# SparkFun_LoRaSerial_915MHz_-_1W.net
KiCad netlist of a schematic drawn in EAGLE
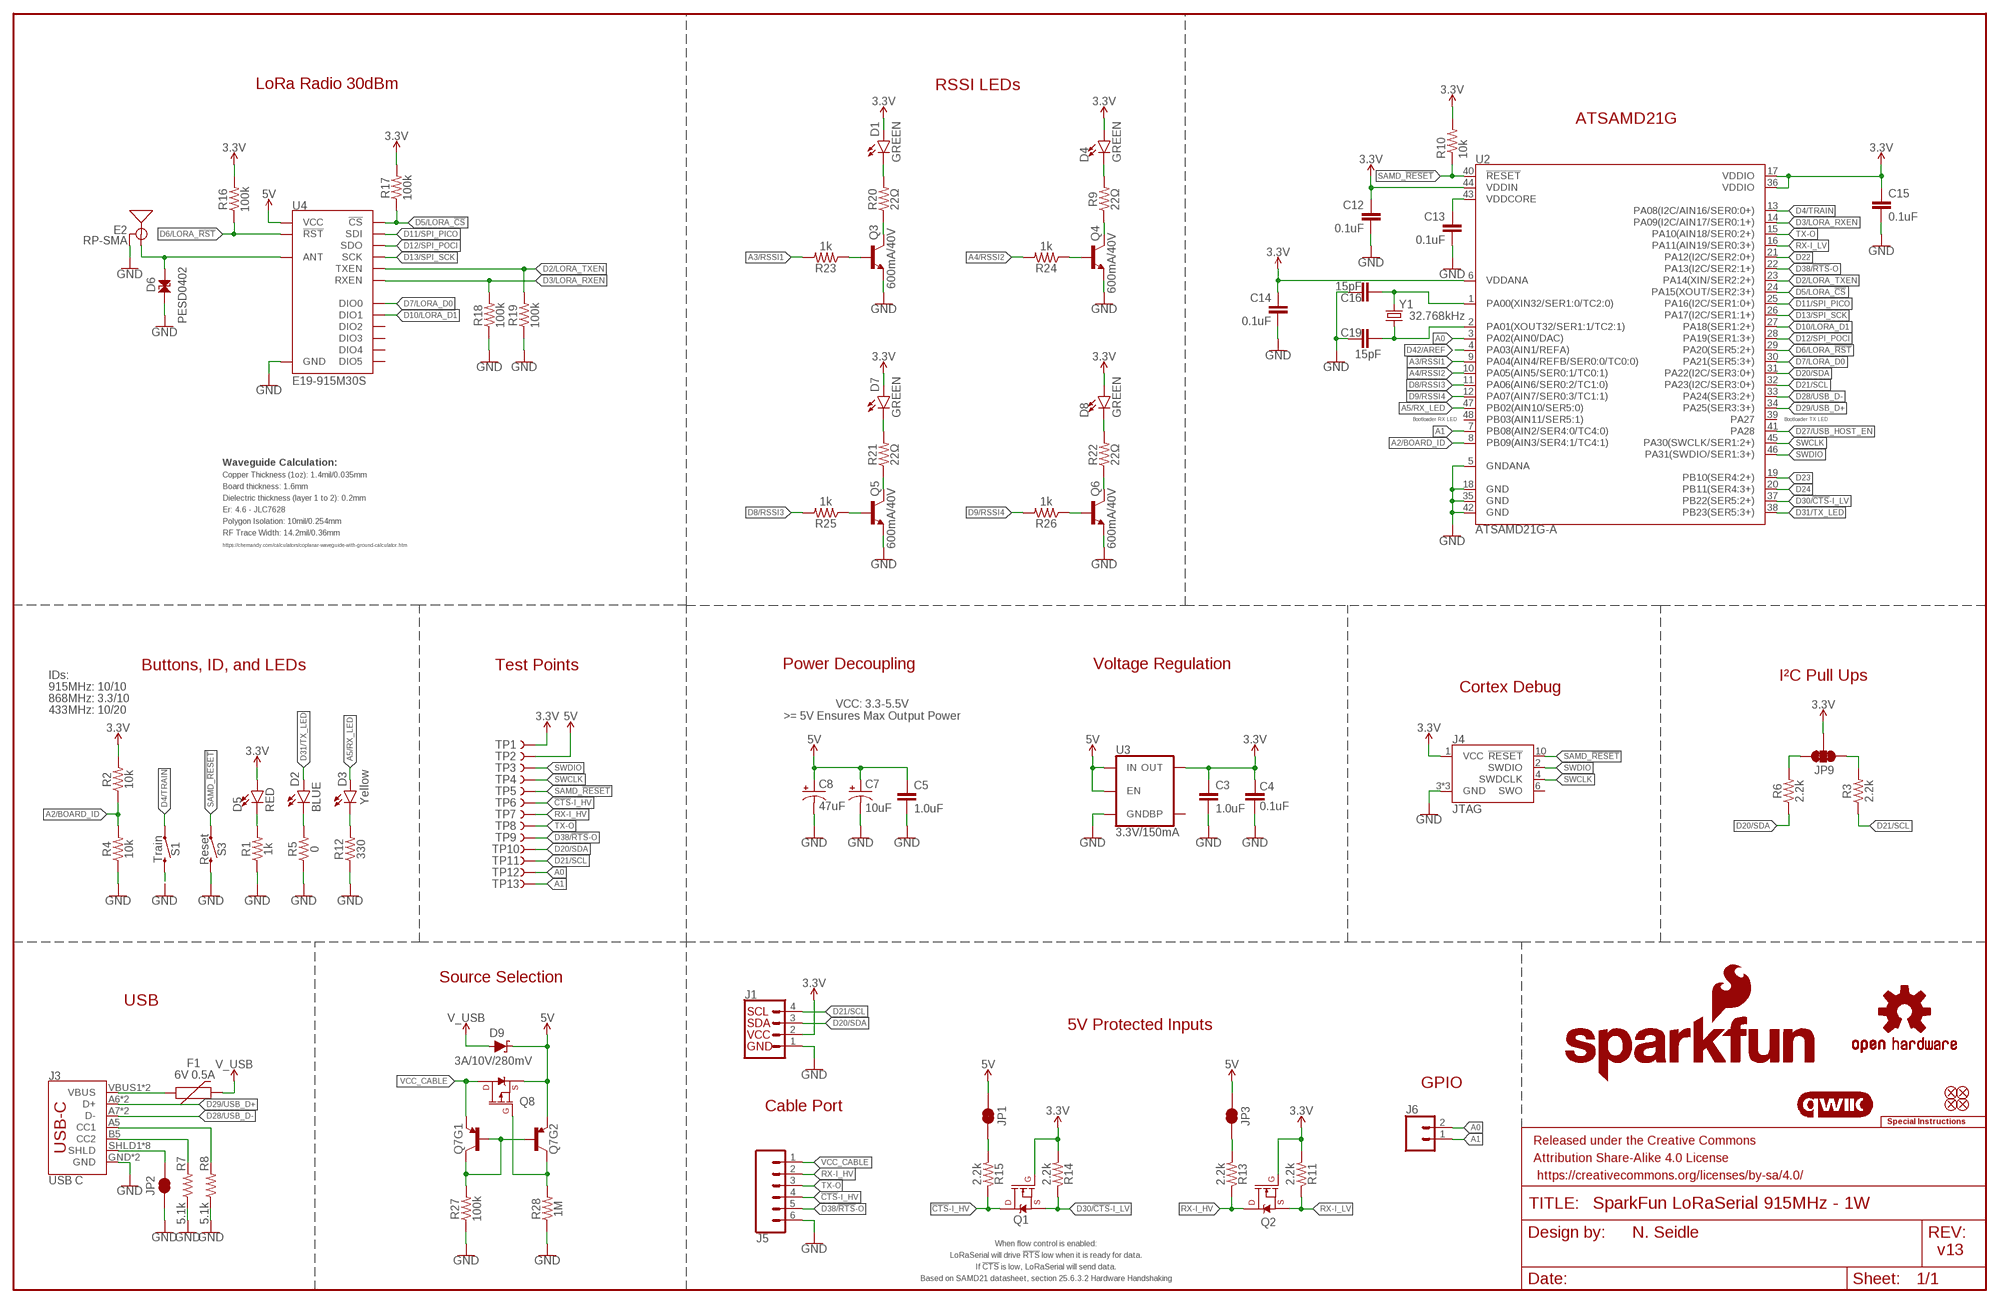
[diagram p0: schematic, sheet 1]

(export (version "E")
  (design (tool "Eeschema 10.0.6"))
  (components
    (comp (ref "C3")
      (value "1.0uF")
      (footprint "eagle-import:0603")
      (libsource (lib "eagle-import") (part "1.0UF-0603-16V-10%-X7R"))
    )
    (comp (ref "C4")
      (value "0.1uF")
      (footprint "eagle-import:0603")
      (libsource (lib "eagle-import") (part "0.1UF-0603-25V-5%"))
    )
    (comp (ref "C5")
      (value "1.0uF")
      (footprint "eagle-import:0603")
      (libsource (lib "eagle-import") (part "1.0UF-0603-16V-10%-X7R"))
    )
    (comp (ref "C7")
      (value "10uF")
      (footprint "eagle-import:EIA3216")
      (libsource (lib "eagle-import") (part "10UF-POLAR-EIA3216-16V-10%(TANT)"))
    )
    (comp (ref "C8")
      (value "47uF")
      (footprint "eagle-import:EIA3528")
      (libsource (lib "eagle-import") (part "47UF-POLAR-EIA3528-10V-10%"))
    )
    (comp (ref "C12")
      (value "0.1uF")
      (footprint "eagle-import:0603")
      (libsource (lib "eagle-import") (part "0.1UF-0603-25V-(+80/-20%)"))
    )
    (comp (ref "C13")
      (value "0.1uF")
      (footprint "eagle-import:0603")
      (libsource (lib "eagle-import") (part "0.1UF-0603-25V-(+80/-20%)"))
    )
    (comp (ref "C14")
      (value "0.1uF")
      (footprint "eagle-import:0603")
      (libsource (lib "eagle-import") (part "0.1UF-0603-25V-(+80/-20%)"))
    )
    (comp (ref "C15")
      (value "0.1uF")
      (footprint "eagle-import:0603")
      (libsource (lib "eagle-import") (part "0.1UF-0603-25V-(+80/-20%)"))
    )
    (comp (ref "C16")
      (value "15pF")
      (footprint "eagle-import:0603")
      (libsource (lib "eagle-import") (part "15PF-0603-50V-5%"))
    )
    (comp (ref "C19")
      (value "15pF")
      (footprint "eagle-import:0603")
      (libsource (lib "eagle-import") (part "15PF-0603-50V-5%"))
    )
    (comp (ref "D1")
      (value "GREEN")
      (footprint "eagle-import:LED-0603")
      (libsource (lib "eagle-import") (part "LED-GREEN0603"))
    )
    (comp (ref "D2")
      (value "BLUE")
      (footprint "eagle-import:LED-0603")
      (libsource (lib "eagle-import") (part "LED-BLUE0603"))
    )
    (comp (ref "D3")
      (value "Yellow")
      (footprint "eagle-import:LED-0603")
      (libsource (lib "eagle-import") (part "LED-YELLOW0603"))
    )
    (comp (ref "D4")
      (value "GREEN")
      (footprint "eagle-import:LED-0603")
      (libsource (lib "eagle-import") (part "LED-GREEN0603"))
    )
    (comp (ref "D5")
      (value "RED")
      (footprint "eagle-import:LED-0603")
      (libsource (lib "eagle-import") (part "LED-RED0603"))
    )
    (comp (ref "D6")
      (value "PESD0402")
      (footprint "eagle-import:0402-TIGHT")
      (libsource (lib "eagle-import") (part "PESD0402-0402T"))
    )
    (comp (ref "D7")
      (value "GREEN")
      (footprint "eagle-import:LED-0603")
      (libsource (lib "eagle-import") (part "LED-GREEN0603"))
    )
    (comp (ref "D8")
      (value "GREEN")
      (footprint "eagle-import:LED-0603")
      (libsource (lib "eagle-import") (part "LED-GREEN0603"))
    )
    (comp (ref "D9")
      (value "3A/10V/280mV")
      (footprint "eagle-import:SOD-323")
      (libsource (lib "eagle-import") (part "DIODE-SCHOTTKY-BAT60A"))
    )
    (comp (ref "E2")
      (value "RP-SMA")
      (footprint "eagle-import:RP-SMA-EDGE")
      (libsource (lib "eagle-import") (part "ANTENNA-SMA-GROUNDEDEDGE_RPSMA"))
    )
    (comp (ref "F1")
      (value "6V 0.5A")
      (footprint "eagle-import:0805")
      (libsource (lib "eagle-import") (part "PPTC_6V500MA"))
    )
    (comp (ref "FID1")
      (value "FIDUCIAL1X2")
      (footprint "eagle-import:FIDUCIAL-1X2")
      (libsource (lib "eagle-import") (part "FIDUCIAL1X2"))
    )
    (comp (ref "FID2")
      (value "FIDUCIAL1X2")
      (footprint "eagle-import:FIDUCIAL-1X2")
      (libsource (lib "eagle-import") (part "FIDUCIAL1X2"))
    )
    (comp (ref "FID3")
      (value "FIDUCIAL1X2")
      (footprint "eagle-import:FIDUCIAL-1X2")
      (libsource (lib "eagle-import") (part "FIDUCIAL1X2"))
    )
    (comp (ref "FID4")
      (value "FIDUCIAL1X2")
      (footprint "eagle-import:FIDUCIAL-1X2")
      (libsource (lib "eagle-import") (part "FIDUCIAL1X2"))
    )
    (comp (ref "FRAME3")
      (value "FRAME-LEDGER")
      (footprint "eagle-import:CREATIVE_COMMONS")
      (libsource (lib "eagle-import") (part "FRAME-LEDGER"))
    )
    (comp (ref "J1")
      (value "QWIIC_RIGHT_ANGLE")
      (footprint "eagle-import:JST04_1MM_RA")
      (libsource (lib "eagle-import") (part "QWIIC_CONNECTORJS-1MM"))
    )
    (comp (ref "J3")
      (value "USB C")
      (footprint "eagle-import:USB-C-16P")
      (libsource (lib "eagle-import") (part "USB_C16PIN"))
    )
    (comp (ref "J4")
      (value "JTAG")
      (footprint "eagle-import:2X5-PTH-1.27MM-NO_SILK")
      (libsource (lib "eagle-import") (part "CORTEX_JTAG_DEBUG_MINIMUM_PTH_NS"))
    )
    (comp (ref "J5")
      (value "CONN_06JST-SMD-LOCKING")
      (footprint "eagle-import:JST-6-SMD-1.25MM-LOCKING")
      (libsource (lib "eagle-import") (part "CONN_06JST-SMD-LOCKING"))
    )
    (comp (ref "J6")
      (value "CONN_021X02_NO_SILK")
      (footprint "eagle-import:1X02_NO_SILK")
      (libsource (lib "eagle-import") (part "CONN_021X02_NO_SILK"))
    )
    (comp (ref "JP1")
      (value "JUMPER-SMT_2_NC_TRACE_SILK")
      (footprint "eagle-import:SMT-JUMPER_2_NC_TRACE_SILK")
      (libsource (lib "eagle-import") (part "JUMPER-SMT_2_NC_TRACE_SILK"))
    )
    (comp (ref "JP2")
      (value "JUMPER-SMT_2_NC_TRACE_SILK")
      (footprint "eagle-import:SMT-JUMPER_2_NC_TRACE_SILK")
      (libsource (lib "eagle-import") (part "JUMPER-SMT_2_NC_TRACE_SILK"))
    )
    (comp (ref "JP3")
      (value "JUMPER-SMT_2_NC_TRACE_SILK")
      (footprint "eagle-import:SMT-JUMPER_2_NC_TRACE_SILK")
      (libsource (lib "eagle-import") (part "JUMPER-SMT_2_NC_TRACE_SILK"))
    )
    (comp (ref "JP9")
      (value "JUMPER-SMT_3_2-NC_TRACE_SILK")
      (footprint "eagle-import:SMT-JUMPER_3_2-NC_TRACE_SILK")
      (libsource (lib "eagle-import") (part "JUMPER-SMT_3_2-NC_TRACE_SILK"))
    )
    (comp (ref "LOGO1")
      (value "SPECIAL_INSTRUCTIONS-ORDERING")
      (footprint "eagle-import:ORDERING_INSTRUCTIONS")
      (libsource (lib "eagle-import") (part "SPECIAL_INSTRUCTIONS-ORDERING"))
    )
    (comp (ref "LOGO2")
      (value "SFE_LOGO_NAME_FLAME9_MM")
      (footprint "eagle-import:SFE_LOGO_NAME_FLAME_9MM")
      (libsource (lib "eagle-import") (part "SFE_LOGO_NAME_FLAME9_MM"))
    )
    (comp (ref "LOGO3")
      (value "QWIIC_LOGO_CONNECTOR")
      (footprint "eagle-import:QWIIC_5.5MM")
      (libsource (lib "eagle-import") (part "QWIIC_LOGO_CONNECTOR"))
    )
    (comp (ref "LOGO4")
      (value "OSHW-LOGOMINI")
      (footprint "eagle-import:OSHW-LOGO-MINI")
      (libsource (lib "eagle-import") (part "OSHW-LOGOMINI"))
    )
    (comp (ref "LOGO5")
      (value "SFE_LOGO_NAME9_MM")
      (footprint "eagle-import:SFE_LOGO_NAME_9MM")
      (libsource (lib "eagle-import") (part "SFE_LOGO_NAME9_MM"))
    )
    (comp (ref "Q1")
      (value "20V/0.2A/8MHz/1.2Ω/1Vth")
      (footprint "eagle-import:SOT-416FL")
      (libsource (lib "eagle-import") (part "MOSFET-NCH-RE1C002UNTCL"))
    )
    (comp (ref "Q2")
      (value "20V/0.2A/8MHz/1.2Ω/1Vth")
      (footprint "eagle-import:SOT-416FL")
      (libsource (lib "eagle-import") (part "MOSFET-NCH-RE1C002UNTCL"))
    )
    (comp (ref "Q3")
      (value "600mA/40V")
      (footprint "eagle-import:SOT23-3")
      (libsource (lib "eagle-import") (part "TRANS_NPN-MMBT2222AL"))
    )
    (comp (ref "Q4")
      (value "600mA/40V")
      (footprint "eagle-import:SOT23-3")
      (libsource (lib "eagle-import") (part "TRANS_NPN-MMBT2222AL"))
    )
    (comp (ref "Q5")
      (value "600mA/40V")
      (footprint "eagle-import:SOT23-3")
      (libsource (lib "eagle-import") (part "TRANS_NPN-MMBT2222AL"))
    )
    (comp (ref "Q6")
      (value "600mA/40V")
      (footprint "eagle-import:SOT23-3")
      (libsource (lib "eagle-import") (part "TRANS_NPN-MMBT2222AL"))
    )
    (comp (ref "Q7")
      (value "TRANS_PNP_DUALSOT-363")
      (footprint "eagle-import:SOT363_PHILIPS")
      (libsource (lib "eagle-import") (part "TRANS_PNP_DUALSOT-363"))
    )
    (comp (ref "Q8")
      (value "20V/4.2A/52mΩ/1.4W")
      (footprint "eagle-import:SOT23-3")
      (libsource (lib "eagle-import") (part "MOSFET_PCH-DMG2305UX-7"))
    )
    (comp (ref "R1")
      (value "1k")
      (footprint "eagle-import:0603")
      (libsource (lib "eagle-import") (part "1KOHM-0603-1/10W-1%"))
    )
    (comp (ref "R2")
      (value "10k")
      (footprint "eagle-import:0603")
      (libsource (lib "eagle-import") (part "10KOHM-0603-1/10W-1%"))
    )
    (comp (ref "R3")
      (value "2.2k")
      (footprint "eagle-import:0603")
      (libsource (lib "eagle-import") (part "2.2KOHM-0603-1/10W-1%"))
    )
    (comp (ref "R4")
      (value "10k")
      (footprint "eagle-import:0603")
      (libsource (lib "eagle-import") (part "10KOHM-0603-1/10W-1%"))
    )
    (comp (ref "R5")
      (value "0")
      (footprint "eagle-import:0603")
      (libsource (lib "eagle-import") (part "0OHM-0603-1/10W"))
    )
    (comp (ref "R6")
      (value "2.2k")
      (footprint "eagle-import:0603")
      (libsource (lib "eagle-import") (part "2.2KOHM-0603-1/10W-1%"))
    )
    (comp (ref "R7")
      (value "5.1k")
      (footprint "eagle-import:0603")
      (libsource (lib "eagle-import") (part "5.1KOHM5.1KOHM-0603-1/10W-1%"))
    )
    (comp (ref "R8")
      (value "5.1k")
      (footprint "eagle-import:0603")
      (libsource (lib "eagle-import") (part "5.1KOHM5.1KOHM-0603-1/10W-1%"))
    )
    (comp (ref "R9")
      (value "22Ω")
      (footprint "eagle-import:0603")
      (libsource (lib "eagle-import") (part "22OHM-0603-1/10W-1%"))
    )
    (comp (ref "R10")
      (value "10k")
      (footprint "eagle-import:0603")
      (libsource (lib "eagle-import") (part "10KOHM-0603-1/10W-1%"))
    )
    (comp (ref "R11")
      (value "2.2k")
      (footprint "eagle-import:0603")
      (libsource (lib "eagle-import") (part "2.2KOHM-0603-1/10W-1%"))
    )
    (comp (ref "R12")
      (value "330")
      (footprint "eagle-import:0603")
      (libsource (lib "eagle-import") (part "330OHM-0603-1/10W-1%"))
    )
    (comp (ref "R13")
      (value "2.2k")
      (footprint "eagle-import:0603")
      (libsource (lib "eagle-import") (part "2.2KOHM-0603-1/10W-1%"))
    )
    (comp (ref "R14")
      (value "2.2k")
      (footprint "eagle-import:0603")
      (libsource (lib "eagle-import") (part "2.2KOHM-0603-1/10W-1%"))
    )
    (comp (ref "R15")
      (value "2.2k")
      (footprint "eagle-import:0603")
      (libsource (lib "eagle-import") (part "2.2KOHM-0603-1/10W-1%"))
    )
    (comp (ref "R16")
      (value "100k")
      (footprint "eagle-import:0603")
      (libsource (lib "eagle-import") (part "100KOHM-0603-1/10W-1%"))
    )
    (comp (ref "R17")
      (value "100k")
      (footprint "eagle-import:0603")
      (libsource (lib "eagle-import") (part "100KOHM-0603-1/10W-1%"))
    )
    (comp (ref "R18")
      (value "100k")
      (footprint "eagle-import:0603")
      (libsource (lib "eagle-import") (part "100KOHM-0603-1/10W-1%"))
    )
    (comp (ref "R19")
      (value "100k")
      (footprint "eagle-import:0603")
      (libsource (lib "eagle-import") (part "100KOHM-0603-1/10W-1%"))
    )
    (comp (ref "R20")
      (value "22Ω")
      (footprint "eagle-import:0603")
      (libsource (lib "eagle-import") (part "22OHM-0603-1/10W-1%"))
    )
    (comp (ref "R21")
      (value "22Ω")
      (footprint "eagle-import:0603")
      (libsource (lib "eagle-import") (part "22OHM-0603-1/10W-1%"))
    )
    (comp (ref "R22")
      (value "22Ω")
      (footprint "eagle-import:0603")
      (libsource (lib "eagle-import") (part "22OHM-0603-1/10W-1%"))
    )
    (comp (ref "R23")
      (value "1k")
      (footprint "eagle-import:0603")
      (libsource (lib "eagle-import") (part "1KOHM-0603-1/10W-1%"))
    )
    (comp (ref "R24")
      (value "1k")
      (footprint "eagle-import:0603")
      (libsource (lib "eagle-import") (part "1KOHM-0603-1/10W-1%"))
    )
    (comp (ref "R25")
      (value "1k")
      (footprint "eagle-import:0603")
      (libsource (lib "eagle-import") (part "1KOHM-0603-1/10W-1%"))
    )
    (comp (ref "R26")
      (value "1k")
      (footprint "eagle-import:0603")
      (libsource (lib "eagle-import") (part "1KOHM-0603-1/10W-1%"))
    )
    (comp (ref "R27")
      (value "100k")
      (footprint "eagle-import:0603")
      (libsource (lib "eagle-import") (part "100KOHM-0603-1/10W-1%"))
    )
    (comp (ref "R28")
      (value "1M")
      (footprint "eagle-import:0603")
      (libsource (lib "eagle-import") (part "1MOHM-0603-1/4W-5%"))
    )
    (comp (ref "S1")
      (value "Train")
      (footprint "eagle-import:TACTILE_SWITCH_SMD_RIGHT_ANGLE")
      (libsource (lib "eagle-import") (part "MOMENTARY-SWITCH-SPST-SMD-RIGHT-ANGLE"))
    )
    (comp (ref "S3")
      (value "Reset")
      (footprint "eagle-import:TACTILE_SWITCH_SMD_5.2MM")
      (libsource (lib "eagle-import") (part "MOMENTARY-SWITCH-SPST-SMD-5.2-TALL-REDUNDANT"))
    )
    (comp (ref "TP1")
      (value "TEST-POINT3X5")
      (footprint "eagle-import:PAD.03X.05")
      (libsource (lib "eagle-import") (part "TEST-POINT3X5"))
    )
    (comp (ref "TP2")
      (value "TEST-POINT3X5")
      (footprint "eagle-import:PAD.03X.05")
      (libsource (lib "eagle-import") (part "TEST-POINT3X5"))
    )
    (comp (ref "TP3")
      (value "TEST-POINT3X5")
      (footprint "eagle-import:PAD.03X.05")
      (libsource (lib "eagle-import") (part "TEST-POINT3X5"))
    )
    (comp (ref "TP4")
      (value "TEST-POINT3X5")
      (footprint "eagle-import:PAD.03X.05")
      (libsource (lib "eagle-import") (part "TEST-POINT3X5"))
    )
    (comp (ref "TP5")
      (value "TEST-POINT3X5")
      (footprint "eagle-import:PAD.03X.05")
      (libsource (lib "eagle-import") (part "TEST-POINT3X5"))
    )
    (comp (ref "TP6")
      (value "TEST-POINT3X5")
      (footprint "eagle-import:PAD.03X.05")
      (libsource (lib "eagle-import") (part "TEST-POINT3X5"))
    )
    (comp (ref "TP7")
      (value "TEST-POINT3X5")
      (footprint "eagle-import:PAD.03X.05")
      (libsource (lib "eagle-import") (part "TEST-POINT3X5"))
    )
    (comp (ref "TP8")
      (value "TEST-POINT3X5")
      (footprint "eagle-import:PAD.03X.05")
      (libsource (lib "eagle-import") (part "TEST-POINT3X5"))
    )
    (comp (ref "TP9")
      (value "TEST-POINT3X5")
      (footprint "eagle-import:PAD.03X.05")
      (libsource (lib "eagle-import") (part "TEST-POINT3X5"))
    )
    (comp (ref "TP10")
      (value "TEST-POINT3X5")
      (footprint "eagle-import:PAD.03X.05")
      (libsource (lib "eagle-import") (part "TEST-POINT3X5"))
    )
    (comp (ref "TP11")
      (value "TEST-POINT3X5")
      (footprint "eagle-import:PAD.03X.05")
      (libsource (lib "eagle-import") (part "TEST-POINT3X5"))
    )
    (comp (ref "TP12")
      (value "TEST-POINT3X5")
      (footprint "eagle-import:PAD.03X.05")
      (libsource (lib "eagle-import") (part "TEST-POINT3X5"))
    )
    (comp (ref "TP13")
      (value "TEST-POINT3X5")
      (footprint "eagle-import:PAD.03X.05")
      (libsource (lib "eagle-import") (part "TEST-POINT3X5"))
    )
    (comp (ref "U2")
      (value "ATSAMD21G-A")
      (footprint "eagle-import:TQFP-48")
      (libsource (lib "eagle-import") (part "ATSAMD21G-A"))
    )
    (comp (ref "U3")
      (value "3.3V/150mA")
      (footprint "eagle-import:SOT23-5")
      (libsource (lib "eagle-import") (part "V_REG_MIC52053.3V"))
    )
    (comp (ref "U4")
      (value "E19-915M30S")
      (footprint "eagle-import:E19-915M30S")
      (libsource (lib "eagle-import") (part "LORA-E19915MHZ"))
    )
    (comp (ref "Y1")
      (value "32.768kHz")
      (footprint "eagle-import:CRYSTAL-SMD-3.2X1.5MM")
      (libsource (lib "eagle-import") (part "CRYSTAL3.2X1.5MM"))
    )
  )
  (nets
    (net (code "1") (name "/D5{slash}LORA_~{CS}") (class "Default")
      (node (ref "R17") (pin "1") (pinfunction "1_1") (pintype "passive"))
      (node (ref "U2") (pin "24") (pinfunction "PA15(XOUT/SER2:3+)_24") (pintype "bidirectional"))
      (node (ref "U4") (pin "15") (pinfunction "~{CS}_15") (pintype "bidirectional"))
    )
    (net (code "2") (name "/D6{slash}LORA_~{RST}") (class "Default")
      (node (ref "R16") (pin "1") (pinfunction "1_1") (pintype "passive"))
      (node (ref "U2") (pin "29") (pinfunction "PA20(SER5:2+)_29") (pintype "bidirectional"))
      (node (ref "U4") (pin "8") (pinfunction "~{RST}_8") (pintype "bidirectional"))
    )
    (net (code "3") (name "/D30{slash}~{CTS}-I_LV") (class "Default")
      (node (ref "Q1") (pin "2") (pinfunction "S_2") (pintype "bidirectional"))
      (node (ref "R14") (pin "1") (pinfunction "1_1") (pintype "passive"))
      (node (ref "U2") (pin "37") (pinfunction "PB22(SER5:2+)_37") (pintype "bidirectional"))
    )
    (net (code "4") (name "/D38{slash}~{RTS}-O") (class "Default")
      (node (ref "J5") (pin "5") (pinfunction "5_5") (pintype "passive"))
      (node (ref "TP9") (pin "1") (pinfunction "1_1") (pintype "bidirectional"))
      (node (ref "U2") (pin "22") (pinfunction "PA13(I2C/SER2:1+)_22") (pintype "bidirectional"))
    )
    (net (code "5") (name "/SAMD_~{RESET}") (class "Default")
      (node (ref "J4") (pin "10") (pinfunction "~{RESET}_10") (pintype "bidirectional"))
      (node (ref "R10") (pin "1") (pinfunction "1_1") (pintype "passive"))
      (node (ref "S3") (pin "1") (pinfunction "1_1") (pintype "passive"))
      (node (ref "S3") (pin "2") (pinfunction "1_2") (pintype "passive"))
      (node (ref "TP5") (pin "1") (pinfunction "1_1") (pintype "bidirectional"))
      (node (ref "U2") (pin "40") (pinfunction "~{RESET}_40") (pintype "bidirectional"))
    )
    (net (code "6") (name "/~{CTS}-I_HV") (class "Default")
      (node (ref "J5") (pin "4") (pinfunction "4_4") (pintype "passive"))
      (node (ref "Q1") (pin "3") (pinfunction "D_3") (pintype "bidirectional"))
      (node (ref "R15") (pin "1") (pinfunction "1_1") (pintype "passive"))
      (node (ref "TP6") (pin "1") (pinfunction "1_1") (pintype "bidirectional"))
    )
    (net (code "7") (name "3.3V") (class "Default")
      (node (ref "C12") (pin "1") (pinfunction "1_1") (pintype "passive"))
      (node (ref "C14") (pin "1") (pinfunction "1_1") (pintype "passive"))
      (node (ref "C15") (pin "1") (pinfunction "1_1") (pintype "passive"))
      (node (ref "C3") (pin "1") (pinfunction "1_1") (pintype "passive"))
      (node (ref "C4") (pin "2") (pinfunction "2_2") (pintype "passive"))
      (node (ref "D1") (pin "A") (pinfunction "A_A") (pintype "passive"))
      (node (ref "D4") (pin "A") (pinfunction "A_A") (pintype "passive"))
      (node (ref "D5") (pin "A") (pinfunction "A_A") (pintype "passive"))
      (node (ref "D7") (pin "A") (pinfunction "A_A") (pintype "passive"))
      (node (ref "D8") (pin "A") (pinfunction "A_A") (pintype "passive"))
      (node (ref "J1") (pin "2") (pinfunction "2_2") (pintype "power_in"))
      (node (ref "J4") (pin "1") (pinfunction "VCC_1") (pintype "bidirectional"))
      (node (ref "JP9") (pin "2") (pinfunction "2_2") (pintype "passive"))
      (node (ref "Q1") (pin "1") (pinfunction "G_1") (pintype "bidirectional"))
      (node (ref "Q2") (pin "1") (pinfunction "G_1") (pintype "bidirectional"))
      (node (ref "R10") (pin "2") (pinfunction "2_2") (pintype "passive"))
      (node (ref "R11") (pin "2") (pinfunction "2_2") (pintype "passive"))
      (node (ref "R14") (pin "2") (pinfunction "2_2") (pintype "passive"))
      (node (ref "R16") (pin "2") (pinfunction "2_2") (pintype "passive"))
      (node (ref "R17") (pin "2") (pinfunction "2_2") (pintype "passive"))
      (node (ref "R2") (pin "2") (pinfunction "2_2") (pintype "passive"))
      (node (ref "TP1") (pin "1") (pinfunction "1_1") (pintype "bidirectional"))
      (node (ref "U2") (pin "17") (pinfunction "VDDIO_17") (pintype "bidirectional"))
      (node (ref "U2") (pin "36") (pinfunction "VDDIO_36") (pintype "bidirectional"))
      (node (ref "U2") (pin "44") (pinfunction "VDDIN_44") (pintype "bidirectional"))
      (node (ref "U2") (pin "6") (pinfunction "VDDANA_6") (pintype "bidirectional"))
      (node (ref "U3") (pin "5") (pinfunction "OUT_5") (pintype "passive"))
    )
    (net (code "8") (name "5V") (class "Default")
      (node (ref "C5") (pin "1") (pinfunction "1_1") (pintype "passive"))
      (node (ref "C7") (pin "+") (pinfunction "+_+") (pintype "passive"))
      (node (ref "C8") (pin "A") (pinfunction "+_A") (pintype "passive"))
      (node (ref "D9") (pin "C") (pinfunction "C_C") (pintype "passive"))
      (node (ref "JP1") (pin "2") (pinfunction "2_2") (pintype "passive"))
      (node (ref "JP3") (pin "2") (pinfunction "2_2") (pintype "passive"))
      (node (ref "Q7") (pin "4") (pinfunction "E_4") (pintype "passive"))
      (node (ref "Q8") (pin "2") (pinfunction "S_2") (pintype "bidirectional"))
      (node (ref "TP2") (pin "1") (pinfunction "1_1") (pintype "bidirectional"))
      (node (ref "U3") (pin "1") (pinfunction "IN_1") (pintype "input"))
      (node (ref "U3") (pin "3") (pinfunction "EN_3") (pintype "input"))
      (node (ref "U4") (pin "11") (pinfunction "VCC_11") (pintype "bidirectional"))
    )
    (net (code "9") (name "A0") (class "Default")
      (node (ref "J6") (pin "2") (pinfunction "2_2") (pintype "passive"))
      (node (ref "TP12") (pin "1") (pinfunction "1_1") (pintype "bidirectional"))
      (node (ref "U2") (pin "3") (pinfunction "PA02(AIN0/DAC)_3") (pintype "bidirectional"))
    )
    (net (code "10") (name "A1") (class "Default")
      (node (ref "J6") (pin "1") (pinfunction "1_1") (pintype "passive"))
      (node (ref "TP13") (pin "1") (pinfunction "1_1") (pintype "bidirectional"))
      (node (ref "U2") (pin "7") (pinfunction "PB08(AIN2/SER4:0/TC4:0)_7") (pintype "bidirectional"))
    )
    (net (code "11") (name "A2{slash}BOARD_ID") (class "Default")
      (node (ref "R2") (pin "1") (pinfunction "1_1") (pintype "passive"))
      (node (ref "R4") (pin "2") (pinfunction "2_2") (pintype "passive"))
      (node (ref "U2") (pin "8") (pinfunction "PB09(AIN3/SER4:1/TC4:1)_8") (pintype "bidirectional"))
    )
    (net (code "12") (name "A3{slash}RSSI1") (class "Default")
      (node (ref "R23") (pin "2") (pinfunction "2_2") (pintype "passive"))
      (node (ref "U2") (pin "9") (pinfunction "PA04(AIN4/REFB/SER0:0/TC0:0)_9") (pintype "bidirectional"))
    )
    (net (code "13") (name "A4{slash}RSSI2") (class "Default")
      (node (ref "R24") (pin "2") (pinfunction "2_2") (pintype "passive"))
      (node (ref "U2") (pin "10") (pinfunction "PA05(AIN5/SER0:1/TC0:1)_10") (pintype "bidirectional"))
    )
    (net (code "14") (name "A5{slash}RX_LED") (class "Default")
      (node (ref "D3") (pin "A") (pinfunction "A_A") (pintype "passive"))
      (node (ref "U2") (pin "47") (pinfunction "PB02(AIN10/SER5:0)_47") (pintype "bidirectional"))
    )
    (net (code "15") (name "D2{slash}LORA_TXEN") (class "Default")
      (node (ref "R19") (pin "2") (pinfunction "2_2") (pintype "passive"))
      (node (ref "U2") (pin "23") (pinfunction "PA14(XIN/SER2:2+)_23") (pintype "bidirectional"))
      (node (ref "U4") (pin "16") (pinfunction "TXEN_16") (pintype "bidirectional"))
    )
    (net (code "16") (name "D3{slash}LORA_RXEN") (class "Default")
      (node (ref "R18") (pin "2") (pinfunction "2_2") (pintype "passive"))
      (node (ref "U2") (pin "14") (pinfunction "PA09(I2C/AIN17/SER0:1+)_14") (pintype "bidirectional"))
      (node (ref "U4") (pin "17") (pinfunction "RXEN_17") (pintype "bidirectional"))
    )
    (net (code "17") (name "D4{slash}TRAIN") (class "Default")
      (node (ref "S1") (pin "1") (pinfunction "1_1") (pintype "passive"))
      (node (ref "U2") (pin "13") (pinfunction "PA08(I2C/AIN16/SER0:0+)_13") (pintype "bidirectional"))
    )
    (net (code "18") (name "D7{slash}LORA_D0") (class "Default")
      (node (ref "U2") (pin "30") (pinfunction "PA21(SER5:3+)_30") (pintype "bidirectional"))
      (node (ref "U4") (pin "7") (pinfunction "DIO0_7") (pintype "bidirectional"))
    )
    (net (code "19") (name "D8{slash}RSSI3") (class "Default")
      (node (ref "R25") (pin "2") (pinfunction "2_2") (pintype "passive"))
      (node (ref "U2") (pin "11") (pinfunction "PA06(AIN6/SER0:2/TC1:0)_11") (pintype "bidirectional"))
    )
    (net (code "20") (name "D9{slash}RSSI4") (class "Default")
      (node (ref "R26") (pin "2") (pinfunction "2_2") (pintype "passive"))
      (node (ref "U2") (pin "12") (pinfunction "PA07(AIN7/SER0:3/TC1:1)_12") (pintype "bidirectional"))
    )
    (net (code "21") (name "D10{slash}LORA_D1") (class "Default")
      (node (ref "U2") (pin "27") (pinfunction "PA18(SER1:2+)_27") (pintype "bidirectional"))
      (node (ref "U4") (pin "6") (pinfunction "DIO1_6") (pintype "bidirectional"))
    )
    (net (code "22") (name "D11{slash}SPI_PICO") (class "Default")
      (node (ref "U2") (pin "25") (pinfunction "PA16(I2C/SER1:0+)_25") (pintype "bidirectional"))
      (node (ref "U4") (pin "14") (pinfunction "SDI_14") (pintype "bidirectional"))
    )
    (net (code "23") (name "D12{slash}SPI_POCI") (class "Default")
      (node (ref "U2") (pin "28") (pinfunction "PA19(SER1:3+)_28") (pintype "bidirectional"))
      (node (ref "U4") (pin "13") (pinfunction "SDO_13") (pintype "bidirectional"))
    )
    (net (code "24") (name "D13{slash}SPI_SCK") (class "Default")
      (node (ref "U2") (pin "26") (pinfunction "PA17(I2C/SER1:1+)_26") (pintype "bidirectional"))
      (node (ref "U4") (pin "12") (pinfunction "SCK_12") (pintype "bidirectional"))
    )
    (net (code "25") (name "D20{slash}SDA") (class "Default")
      (node (ref "J1") (pin "3") (pinfunction "3_3") (pintype "passive"))
      (node (ref "R6") (pin "1") (pinfunction "1_1") (pintype "passive"))
      (node (ref "TP10") (pin "1") (pinfunction "1_1") (pintype "bidirectional"))
      (node (ref "U2") (pin "31") (pinfunction "PA22(I2C/SER3:0+)_31") (pintype "bidirectional"))
    )
    (net (code "26") (name "D21{slash}SCL") (class "Default")
      (node (ref "J1") (pin "4") (pinfunction "4_4") (pintype "passive"))
      (node (ref "R3") (pin "1") (pinfunction "1_1") (pintype "passive"))
      (node (ref "TP11") (pin "1") (pinfunction "1_1") (pintype "bidirectional"))
      (node (ref "U2") (pin "32") (pinfunction "PA23(I2C/SER3:0+)_32") (pintype "bidirectional"))
    )
    (net (code "27") (name "D22") (class "Default")
      (node (ref "U2") (pin "21") (pinfunction "PA12(I2C/SER2:0+)_21") (pintype "bidirectional"))
    )
    (net (code "28") (name "D23") (class "Default")
      (node (ref "U2") (pin "19") (pinfunction "PB10(SER4:2+)_19") (pintype "bidirectional"))
    )
    (net (code "29") (name "D24") (class "Default")
      (node (ref "U2") (pin "20") (pinfunction "PB11(SER4:3+)_20") (pintype "bidirectional"))
    )
    (net (code "30") (name "D27{slash}USB_HOST_EN") (class "Default")
      (node (ref "U2") (pin "41") (pinfunction "PA28_41") (pintype "bidirectional"))
    )
    (net (code "31") (name "D28{slash}USB_D-") (class "Default")
      (node (ref "J3") (pin "A7") (pinfunction "D-_A7") (pintype "bidirectional"))
      (node (ref "J3") (pin "B7") (pinfunction "D-_B7") (pintype "bidirectional"))
      (node (ref "U2") (pin "33") (pinfunction "PA24(SER3:2+)_33") (pintype "bidirectional"))
    )
    (net (code "32") (name "D29{slash}USB_D+") (class "Default")
      (node (ref "J3") (pin "A6") (pinfunction "D+_A6") (pintype "bidirectional"))
      (node (ref "J3") (pin "B6") (pinfunction "D+_B6") (pintype "bidirectional"))
      (node (ref "U2") (pin "34") (pinfunction "PA25(SER3:3+)_34") (pintype "bidirectional"))
    )
    (net (code "33") (name "D31{slash}TX_LED") (class "Default")
      (node (ref "D2") (pin "A") (pinfunction "A_A") (pintype "passive"))
      (node (ref "U2") (pin "38") (pinfunction "PB23(SER5:3+)_38") (pintype "bidirectional"))
    )
    (net (code "34") (name "D42{slash}AREF") (class "Default")
      (node (ref "U2") (pin "4") (pinfunction "PA03(AIN1/REFA)_4") (pintype "bidirectional"))
    )
    (net (code "35") (name "GND") (class "Default")
      (node (ref "C12") (pin "2") (pinfunction "2_2") (pintype "passive"))
      (node (ref "C13") (pin "2") (pinfunction "2_2") (pintype "passive"))
      (node (ref "C14") (pin "2") (pinfunction "2_2") (pintype "passive"))
      (node (ref "C15") (pin "2") (pinfunction "2_2") (pintype "passive"))
      (node (ref "C16") (pin "1") (pinfunction "1_1") (pintype "passive"))
      (node (ref "C19") (pin "2") (pinfunction "2_2") (pintype "passive"))
      (node (ref "C3") (pin "2") (pinfunction "2_2") (pintype "passive"))
      (node (ref "C4") (pin "1") (pinfunction "1_1") (pintype "passive"))
      (node (ref "C5") (pin "2") (pinfunction "2_2") (pintype "passive"))
      (node (ref "C7") (pin "-") (pinfunction "-_-") (pintype "passive"))
      (node (ref "C8") (pin "C") (pinfunction "-_C") (pintype "passive"))
      (node (ref "D6") (pin "1") (pinfunction "1_1") (pintype "bidirectional"))
      (node (ref "E2") (pin "GND@0") (pinfunction "GND_GND@0") (pintype "bidirectional"))
      (node (ref "E2") (pin "GND@1") (pinfunction "GND_GND@1") (pintype "bidirectional"))
      (node (ref "E2") (pin "GND@2") (pinfunction "GND_GND@2") (pintype "bidirectional"))
      (node (ref "E2") (pin "GND@3") (pinfunction "GND_GND@3") (pintype "bidirectional"))
      (node (ref "J1") (pin "1") (pinfunction "1_1") (pintype "power_in"))
      (node (ref "J3") (pin "GND") (pinfunction "GND_GND") (pintype "bidirectional"))
      (node (ref "J3") (pin "GND2") (pinfunction "GND_GND2") (pintype "bidirectional"))
      (node (ref "J4") (pin "3") (pinfunction "GND_3") (pintype "bidirectional"))
      (node (ref "J4") (pin "5") (pinfunction "GND_5") (pintype "bidirectional"))
      (node (ref "J4") (pin "9") (pinfunction "GND_9") (pintype "bidirectional"))
      (node (ref "J5") (pin "6") (pinfunction "6_6") (pintype "passive"))
      (node (ref "JP2") (pin "1") (pinfunction "1_1") (pintype "passive"))
      (node (ref "Q3") (pin "2") (pinfunction "E_2") (pintype "passive"))
      (node (ref "Q4") (pin "2") (pinfunction "E_2") (pintype "passive"))
      (node (ref "Q5") (pin "2") (pinfunction "E_2") (pintype "passive"))
      (node (ref "Q6") (pin "2") (pinfunction "E_2") (pintype "passive"))
      (node (ref "R1") (pin "1") (pinfunction "1_1") (pintype "passive"))
      (node (ref "R12") (pin "1") (pinfunction "1_1") (pintype "passive"))
      (node (ref "R18") (pin "1") (pinfunction "1_1") (pintype "passive"))
      (node (ref "R19") (pin "1") (pinfunction "1_1") (pintype "passive"))
      (node (ref "R27") (pin "1") (pinfunction "1_1") (pintype "passive"))
      (node (ref "R28") (pin "1") (pinfunction "1_1") (pintype "passive"))
      (node (ref "R4") (pin "1") (pinfunction "1_1") (pintype "passive"))
      (node (ref "R5") (pin "1") (pinfunction "1_1") (pintype "passive"))
      (node (ref "R7") (pin "1") (pinfunction "1_1") (pintype "passive"))
      (node (ref "R8") (pin "1") (pinfunction "1_1") (pintype "passive"))
      (node (ref "S1") (pin "2") (pinfunction "2_2") (pintype "passive"))
      (node (ref "S3") (pin "3") (pinfunction "2_3") (pintype "passive"))
      (node (ref "S3") (pin "4") (pinfunction "2_4") (pintype "passive"))
      (node (ref "U2") (pin "18") (pinfunction "GND_18") (pintype "bidirectional"))
      (node (ref "U2") (pin "35") (pinfunction "GND_35") (pintype "bidirectional"))
      (node (ref "U2") (pin "42") (pinfunction "GND_42") (pintype "bidirectional"))
      (node (ref "U2") (pin "5") (pinfunction "GNDANA_5") (pintype "bidirectional"))
      (node (ref "U3") (pin "2") (pinfunction "GND_2") (pintype "input"))
      (node (ref "U4") (pin "1") (pinfunction "GND_1") (pintype "bidirectional"))
      (node (ref "U4") (pin "10") (pinfunction "GND_10") (pintype "bidirectional"))
      (node (ref "U4") (pin "18") (pinfunction "GND_18") (pintype "bidirectional"))
      (node (ref "U4") (pin "20") (pinfunction "GND_20") (pintype "bidirectional"))
      (node (ref "U4") (pin "21") (pinfunction "GND_21") (pintype "bidirectional"))
      (node (ref "U4") (pin "22") (pinfunction "GND_22") (pintype "bidirectional"))
      (node (ref "U4") (pin "9") (pinfunction "GND_9") (pintype "bidirectional"))
    )
    (net (code "36") (name "Net-(D1-PadC)") (class "Default")
      (node (ref "D1") (pin "C") (pinfunction "C_C") (pintype "passive"))
      (node (ref "R20") (pin "2") (pinfunction "2_2") (pintype "passive"))
    )
    (net (code "37") (name "Net-(D2-PadC)") (class "Default")
      (node (ref "D2") (pin "C") (pinfunction "C_C") (pintype "passive"))
      (node (ref "R5") (pin "2") (pinfunction "2_2") (pintype "passive"))
    )
    (net (code "38") (name "Net-(D3-PadC)") (class "Default")
      (node (ref "D3") (pin "C") (pinfunction "C_C") (pintype "passive"))
      (node (ref "R12") (pin "2") (pinfunction "2_2") (pintype "passive"))
    )
    (net (code "39") (name "Net-(D4-PadC)") (class "Default")
      (node (ref "D4") (pin "C") (pinfunction "C_C") (pintype "passive"))
      (node (ref "R9") (pin "2") (pinfunction "2_2") (pintype "passive"))
    )
    (net (code "40") (name "Net-(D5-PadC)") (class "Default")
      (node (ref "D5") (pin "C") (pinfunction "C_C") (pintype "passive"))
      (node (ref "R1") (pin "2") (pinfunction "2_2") (pintype "passive"))
    )
    (net (code "41") (name "Net-(D7-PadC)") (class "Default")
      (node (ref "D7") (pin "C") (pinfunction "C_C") (pintype "passive"))
      (node (ref "R21") (pin "2") (pinfunction "2_2") (pintype "passive"))
    )
    (net (code "42") (name "Net-(D8-PadC)") (class "Default")
      (node (ref "D8") (pin "C") (pinfunction "C_C") (pintype "passive"))
      (node (ref "R22") (pin "2") (pinfunction "2_2") (pintype "passive"))
    )
    (net (code "43") (name "Net-(E2-SIGNAL)") (class "Default")
      (node (ref "D6") (pin "2") (pinfunction "2_2") (pintype "bidirectional"))
      (node (ref "E2") (pin "SIG") (pinfunction "SIGNAL_SIG") (pintype "bidirectional"))
      (node (ref "U4") (pin "19") (pinfunction "ANT_19") (pintype "bidirectional"))
    )
    (net (code "44") (name "Net-(F1-Pad1)") (class "Default")
      (node (ref "F1") (pin "1") (pinfunction "1_1") (pintype "bidirectional"))
      (node (ref "J3") (pin "VBUS1") (pinfunction "VBUS_VBUS1") (pintype "bidirectional"))
      (node (ref "J3") (pin "VBUS2") (pinfunction "VBUS_VBUS2") (pintype "bidirectional"))
    )
    (net (code "45") (name "Net-(J3-CC1)") (class "Default")
      (node (ref "J3") (pin "A5") (pinfunction "CC1_A5") (pintype "bidirectional"))
      (node (ref "R8") (pin "2") (pinfunction "2_2") (pintype "passive"))
    )
    (net (code "46") (name "Net-(J3-CC2)") (class "Default")
      (node (ref "J3") (pin "B5") (pinfunction "CC2_B5") (pintype "bidirectional"))
      (node (ref "R7") (pin "2") (pinfunction "2_2") (pintype "passive"))
    )
    (net (code "47") (name "Net-(J3-SHLD-PadSHLD1)") (class "Default")
      (node (ref "J3") (pin "SHLD1") (pinfunction "SHLD_SHLD1") (pintype "bidirectional"))
      (node (ref "J3") (pin "SHLD2") (pinfunction "SHLD_SHLD2") (pintype "bidirectional"))
      (node (ref "J3") (pin "SHLD3") (pinfunction "SHLD_SHLD3") (pintype "bidirectional"))
      (node (ref "J3") (pin "SHLD4") (pinfunction "SHLD_SHLD4") (pintype "bidirectional"))
      (node (ref "J3") (pin "SHLD5") (pinfunction "SHLD_SHLD5") (pintype "bidirectional"))
      (node (ref "J3") (pin "SHLD6") (pinfunction "SHLD_SHLD6") (pintype "bidirectional"))
      (node (ref "J3") (pin "SHLD7") (pinfunction "SHLD_SHLD7") (pintype "bidirectional"))
      (node (ref "J3") (pin "SHLD8") (pinfunction "SHLD_SHLD8") (pintype "bidirectional"))
      (node (ref "JP2") (pin "2") (pinfunction "2_2") (pintype "passive"))
    )
    (net (code "48") (name "Net-(JP1-Pad1)") (class "Default")
      (node (ref "JP1") (pin "1") (pinfunction "1_1") (pintype "passive"))
      (node (ref "R15") (pin "2") (pinfunction "2_2") (pintype "passive"))
    )
    (net (code "49") (name "Net-(JP3-Pad1)") (class "Default")
      (node (ref "JP3") (pin "1") (pinfunction "1_1") (pintype "passive"))
      (node (ref "R13") (pin "2") (pinfunction "2_2") (pintype "passive"))
    )
    (net (code "50") (name "Net-(JP9-Pad1)") (class "Default")
      (node (ref "JP9") (pin "1") (pinfunction "1_1") (pintype "passive"))
      (node (ref "R3") (pin "2") (pinfunction "2_2") (pintype "passive"))
    )
    (net (code "51") (name "Net-(JP9-Pad3)") (class "Default")
      (node (ref "JP9") (pin "3") (pinfunction "3_3") (pintype "passive"))
      (node (ref "R6") (pin "2") (pinfunction "2_2") (pintype "passive"))
    )
    (net (code "52") (name "Net-(Q3-B)") (class "Default")
      (node (ref "Q3") (pin "1") (pinfunction "B_1") (pintype "passive"))
      (node (ref "R23") (pin "1") (pinfunction "1_1") (pintype "passive"))
    )
    (net (code "53") (name "Net-(Q3-C)") (class "Default")
      (node (ref "Q3") (pin "3") (pinfunction "C_3") (pintype "passive"))
      (node (ref "R20") (pin "1") (pinfunction "1_1") (pintype "passive"))
    )
    (net (code "54") (name "Net-(Q4-B)") (class "Default")
      (node (ref "Q4") (pin "1") (pinfunction "B_1") (pintype "passive"))
      (node (ref "R24") (pin "1") (pinfunction "1_1") (pintype "passive"))
    )
    (net (code "55") (name "Net-(Q4-C)") (class "Default")
      (node (ref "Q4") (pin "3") (pinfunction "C_3") (pintype "passive"))
      (node (ref "R9") (pin "1") (pinfunction "1_1") (pintype "passive"))
    )
    (net (code "56") (name "Net-(Q5-B)") (class "Default")
      (node (ref "Q5") (pin "1") (pinfunction "B_1") (pintype "passive"))
      (node (ref "R25") (pin "1") (pinfunction "1_1") (pintype "passive"))
    )
    (net (code "57") (name "Net-(Q5-C)") (class "Default")
      (node (ref "Q5") (pin "3") (pinfunction "C_3") (pintype "passive"))
      (node (ref "R21") (pin "1") (pinfunction "1_1") (pintype "passive"))
    )
    (net (code "58") (name "Net-(Q6-B)") (class "Default")
      (node (ref "Q6") (pin "1") (pinfunction "B_1") (pintype "passive"))
      (node (ref "R26") (pin "1") (pinfunction "1_1") (pintype "passive"))
    )
    (net (code "59") (name "Net-(Q6-C)") (class "Default")
      (node (ref "Q6") (pin "3") (pinfunction "C_3") (pintype "passive"))
      (node (ref "R22") (pin "1") (pinfunction "1_1") (pintype "passive"))
    )
    (net (code "60") (name "Net-(Q7A-B)") (class "Default")
      (node (ref "Q7") (pin "2") (pinfunction "B_2") (pintype "passive"))
      (node (ref "Q7") (pin "5") (pinfunction "B_5") (pintype "passive"))
      (node (ref "Q7") (pin "6") (pinfunction "C_6") (pintype "passive"))
      (node (ref "R27") (pin "2") (pinfunction "2_2") (pintype "passive"))
    )
    (net (code "61") (name "Net-(Q7B-C)") (class "Default")
      (node (ref "Q7") (pin "3") (pinfunction "C_3") (pintype "passive"))
      (node (ref "Q8") (pin "1") (pinfunction "G_1") (pintype "bidirectional"))
      (node (ref "R28") (pin "2") (pinfunction "2_2") (pintype "passive"))
    )
    (net (code "62") (name "Net-(U2-PA00(XIN32{slash}SER1:0{slash}TC2:0))") (class "Default")
      (node (ref "C16") (pin "2") (pinfunction "2_2") (pintype "passive"))
      (node (ref "U2") (pin "1") (pinfunction "PA00(XIN32/SER1:0/TC2:0)_1") (pintype "bidirectional"))
      (node (ref "Y1") (pin "P$2") (pinfunction "2_P$2") (pintype "passive"))
    )
    (net (code "63") (name "Net-(U2-PA01(XOUT32{slash}SER1:1{slash}TC2:1))") (class "Default")
      (node (ref "C19") (pin "1") (pinfunction "1_1") (pintype "passive"))
      (node (ref "U2") (pin "2") (pinfunction "PA01(XOUT32/SER1:1/TC2:1)_2") (pintype "bidirectional"))
      (node (ref "Y1") (pin "P$1") (pinfunction "1_P$1") (pintype "passive"))
    )
    (net (code "64") (name "Net-(U2-VDDCORE)") (class "Default")
      (node (ref "C13") (pin "1") (pinfunction "1_1") (pintype "passive"))
      (node (ref "U2") (pin "43") (pinfunction "VDDCORE_43") (pintype "bidirectional"))
    )
    (net (code "65") (name "RX-I_HV") (class "Default")
      (node (ref "J5") (pin "2") (pinfunction "2_2") (pintype "passive"))
      (node (ref "Q2") (pin "3") (pinfunction "D_3") (pintype "bidirectional"))
      (node (ref "R13") (pin "1") (pinfunction "1_1") (pintype "passive"))
      (node (ref "TP7") (pin "1") (pinfunction "1_1") (pintype "bidirectional"))
    )
    (net (code "66") (name "RX-I_LV") (class "Default")
      (node (ref "Q2") (pin "2") (pinfunction "S_2") (pintype "bidirectional"))
      (node (ref "R11") (pin "1") (pinfunction "1_1") (pintype "passive"))
      (node (ref "U2") (pin "16") (pinfunction "PA11(AIN19/SER0:3+)_16") (pintype "bidirectional"))
    )
    (net (code "67") (name "SWCLK") (class "Default")
      (node (ref "J4") (pin "4") (pinfunction "SWDCLK_4") (pintype "bidirectional"))
      (node (ref "TP4") (pin "1") (pinfunction "1_1") (pintype "bidirectional"))
      (node (ref "U2") (pin "45") (pinfunction "PA30(SWCLK/SER1:2+)_45") (pintype "bidirectional"))
    )
    (net (code "68") (name "SWDIO") (class "Default")
      (node (ref "J4") (pin "2") (pinfunction "SWDIO_2") (pintype "bidirectional"))
      (node (ref "TP3") (pin "1") (pinfunction "1_1") (pintype "bidirectional"))
      (node (ref "U2") (pin "46") (pinfunction "PA31(SWDIO/SER1:3+)_46") (pintype "bidirectional"))
    )
    (net (code "69") (name "TX-O") (class "Default")
      (node (ref "J5") (pin "3") (pinfunction "3_3") (pintype "passive"))
      (node (ref "TP8") (pin "1") (pinfunction "1_1") (pintype "bidirectional"))
      (node (ref "U2") (pin "15") (pinfunction "PA10(AIN18/SER0:2+)_15") (pintype "bidirectional"))
    )
    (net (code "70") (name "VCC_CABLE") (class "Default")
      (node (ref "J5") (pin "1") (pinfunction "1_1") (pintype "passive"))
      (node (ref "Q7") (pin "1") (pinfunction "E_1") (pintype "passive"))
      (node (ref "Q8") (pin "3") (pinfunction "D_3") (pintype "bidirectional"))
    )
    (net (code "71") (name "V_USB") (class "Default")
      (node (ref "D9") (pin "A") (pinfunction "A_A") (pintype "passive"))
      (node (ref "F1") (pin "2") (pinfunction "2_2") (pintype "bidirectional"))
    )
    (net (code "72") (name "unconnected-(J4-SWO-Pad6)") (class "Default")
      (node (ref "J4") (pin "6") (pinfunction "SWO_6") (pintype "bidirectional"))
    )
    (net (code "73") (name "unconnected-(U2-PA27-Pad39)") (class "Default")
      (node (ref "U2") (pin "39") (pinfunction "PA27_39") (pintype "bidirectional"))
    )
    (net (code "74") (name "unconnected-(U2-PB03(AIN11{slash}SER5:1)-Pad48)") (class "Default")
      (node (ref "U2") (pin "48") (pinfunction "PB03(AIN11/SER5:1)_48") (pintype "bidirectional"))
    )
    (net (code "75") (name "unconnected-(U3-BP-Pad4)") (class "Default")
      (node (ref "U3") (pin "4") (pinfunction "BP_4") (pintype "input"))
    )
    (net (code "76") (name "unconnected-(U4-DIO2-Pad5)") (class "Default")
      (node (ref "U4") (pin "5") (pinfunction "DIO2_5") (pintype "bidirectional"))
    )
    (net (code "77") (name "unconnected-(U4-DIO3-Pad4)") (class "Default")
      (node (ref "U4") (pin "4") (pinfunction "DIO3_4") (pintype "bidirectional"))
    )
    (net (code "78") (name "unconnected-(U4-DIO4-Pad3)") (class "Default")
      (node (ref "U4") (pin "3") (pinfunction "DIO4_3") (pintype "bidirectional"))
    )
    (net (code "79") (name "unconnected-(U4-DIO5-Pad2)") (class "Default")
      (node (ref "U4") (pin "2") (pinfunction "DIO5_2") (pintype "bidirectional"))
    )
  )
)
